# node-base.net
KiCad netlist of a schematic drawn in EAGLE
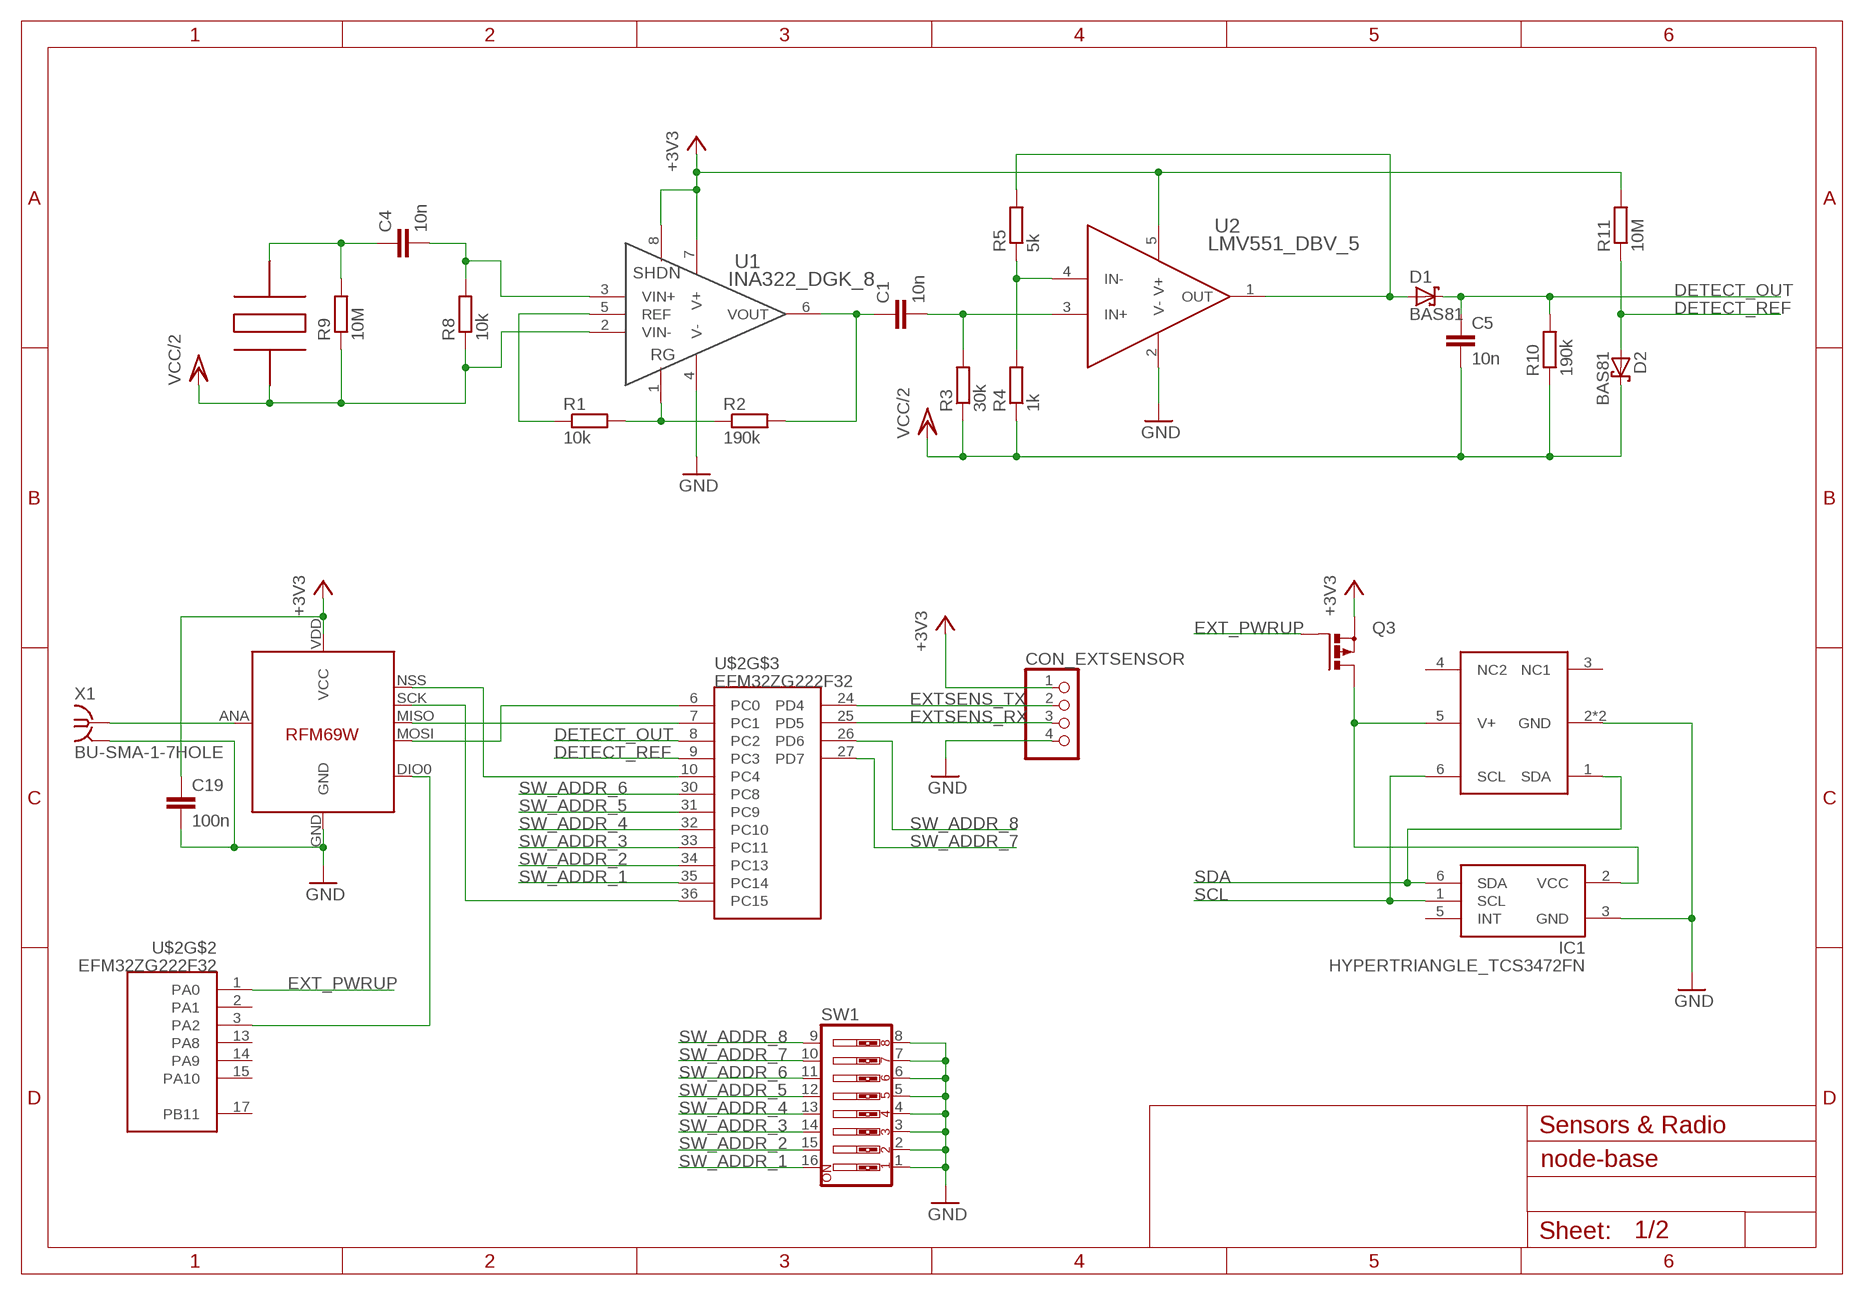
[diagram p0: schematic, sheet 1]
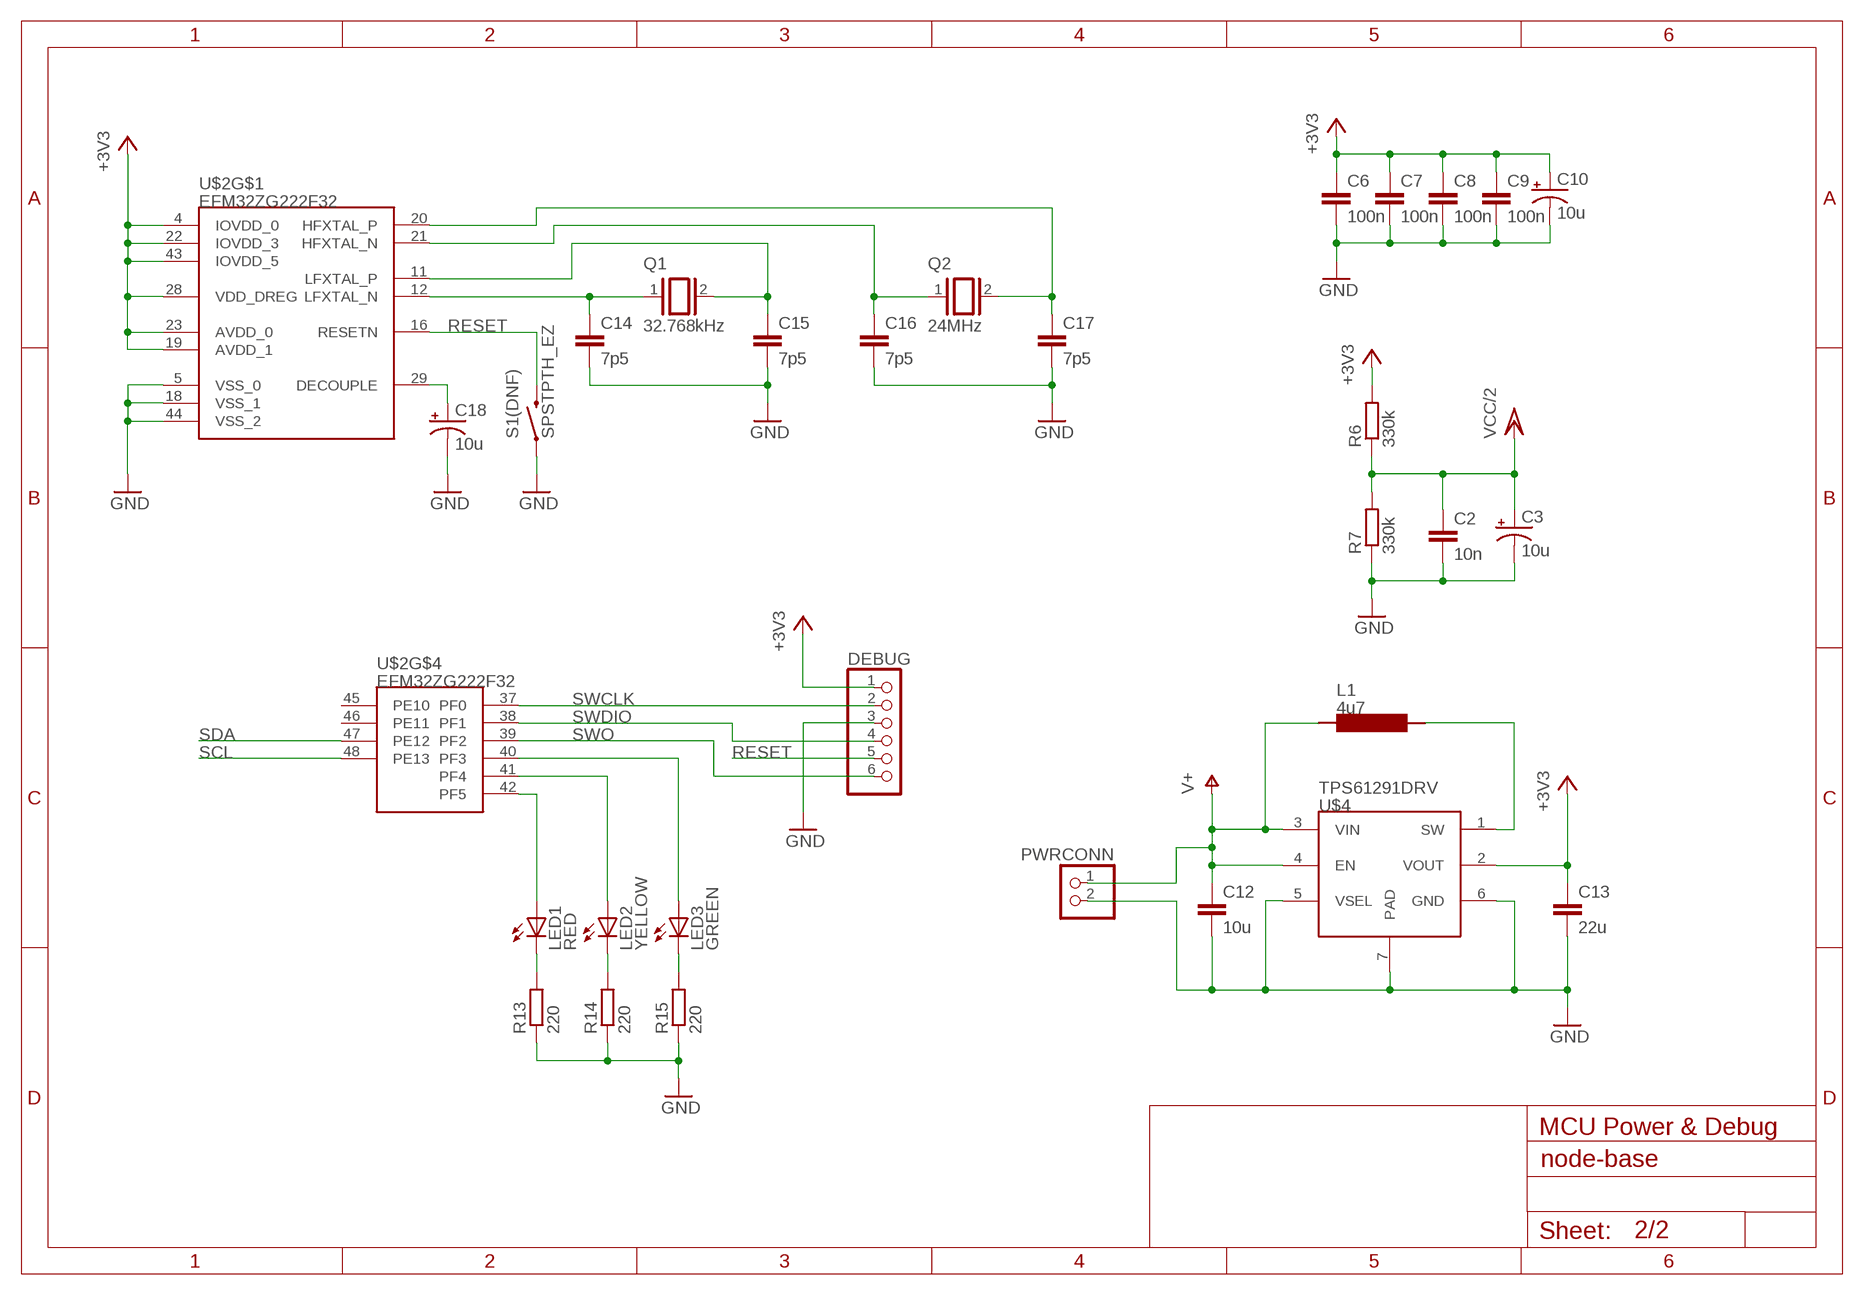
[diagram p1: schematic, sheet 2]

(export (version "E")
  (design (tool "Eeschema 10.0.6"))
  (components
    (comp (ref "C1")
      (value "10n")
      (footprint "eagle-import:CAP-PTH-SMALL")
      (libsource (lib "eagle-import") (part "CAPPTH"))
    )
    (comp (ref "C4")
      (value "10n")
      (footprint "eagle-import:CAP-PTH-SMALL")
      (libsource (lib "eagle-import") (part "CAPPTH"))
    )
    (comp (ref "C5")
      (value "10n")
      (footprint "eagle-import:CAP-PTH-SMALL")
      (libsource (lib "eagle-import") (part "CAPPTH"))
    )
    (comp (ref "C19")
      (value "100n")
      (footprint "eagle-import:CAP-PTH-SMALL")
      (libsource (lib "eagle-import") (part "CAPPTH"))
    )
    (comp (ref "CON_EXTSENSOR")
      (value "PINHD-1X4")
      (footprint "eagle-import:1X04")
      (libsource (lib "eagle-import") (part "PINHD-1X4"))
    )
    (comp (ref "D1")
      (value "BAS81")
      (footprint "eagle-import:DO35-7")
      (libsource (lib "eagle-import") (part "SCHOTTKY-DIODEDO35-7"))
    )
    (comp (ref "D2")
      (value "BAS81")
      (footprint "eagle-import:DO35-7")
      (libsource (lib "eagle-import") (part "SCHOTTKY-DIODEDO35-7"))
    )
    (comp (ref "IC1")
      (value "HYPERTRIANGLE_TCS3472FN")
      (footprint "eagle-import:HYPERTRIANGLE_DFN-6")
      (libsource (lib "eagle-import") (part "HYPERTRIANGLE_TCS3472FN"))
    )
    (comp (ref "Q3")
      (value "PMOSFET_PTO220BH")
      (footprint "eagle-import:TO220BH")
      (libsource (lib "eagle-import") (part "PMOSFET_PTO220BH"))
    )
    (comp (ref "R1")
      (value "10k")
      (footprint "eagle-import:0204_7")
      (libsource (lib "eagle-import") (part "R-EU_0204/7"))
    )
    (comp (ref "R2")
      (value "190k")
      (footprint "eagle-import:0204_7")
      (libsource (lib "eagle-import") (part "R-EU_0204/7"))
    )
    (comp (ref "R3")
      (value "30k")
      (footprint "eagle-import:0204_7")
      (libsource (lib "eagle-import") (part "R-EU_0204/7"))
    )
    (comp (ref "R4")
      (value "1k")
      (footprint "eagle-import:0204_7")
      (libsource (lib "eagle-import") (part "R-EU_0204/7"))
    )
    (comp (ref "R5")
      (value "5k")
      (footprint "eagle-import:0204_7")
      (libsource (lib "eagle-import") (part "R-EU_0204/7"))
    )
    (comp (ref "R8")
      (value "10k")
      (footprint "eagle-import:0204_7")
      (libsource (lib "eagle-import") (part "R-EU_0204/7"))
    )
    (comp (ref "R9")
      (value "10M")
      (footprint "eagle-import:0204_7")
      (libsource (lib "eagle-import") (part "R-EU_0204/7"))
    )
    (comp (ref "R10")
      (value "190k")
      (footprint "eagle-import:0204_7")
      (libsource (lib "eagle-import") (part "R-EU_0204/7"))
    )
    (comp (ref "R11")
      (value "10M")
      (footprint "eagle-import:0204_7")
      (libsource (lib "eagle-import") (part "R-EU_0204/7"))
    )
    (comp (ref "RADIO")
      (value "RFM69")
      (footprint "eagle-import:RFM69W-MINPADS")
      (libsource (lib "eagle-import") (part "RFM69"))
    )
    (comp (ref "SW1")
      (value "SW_DIP-8")
      (footprint "eagle-import:DIPSWITCH-08")
      (libsource (lib "eagle-import") (part "SW_DIP-8"))
    )
    (comp (ref "U$1")
      (value "PIEZOWIREHEADER")
      (footprint "eagle-import:1X02")
      (libsource (lib "eagle-import") (part "PIEZOWIREHEADER"))
    )
    (comp (ref "U$2")
      (value "EFM32ZG222F32")
      (footprint "eagle-import:QFP48")
      (libsource (lib "eagle-import") (part "EFM32ZG222F32"))
    )
    (comp (ref "U$3")
      (value "SHT21")
      (footprint "eagle-import:SHT21")
      (libsource (lib "eagle-import") (part "SHT21"))
    )
    (comp (ref "U1")
      (value "INA322_DGK_8")
      (footprint "eagle-import:DGK8")
      (fields
        (field (name "GENERIC_PART_NUMBER") "INA322")
        (field (name "MANUFACTURER") "Texas Instruments")
        (field (name "MANUFACTURER_PART_NUMBER") "ina322_dgk_8")
      )
      (libsource (lib "eagle-import") (part "INA322_DGK_8"))
    )
    (comp (ref "U2")
      (value "LMV551_DBV_5")
      (footprint "eagle-import:MF05A")
      (libsource (lib "eagle-import") (part "LMV551_DBV_5"))
    )
    (comp (ref "X1")
      (value "BU-SMA-1-7HOLE")
      (footprint "eagle-import:SMA_1-7HOLES")
      (libsource (lib "eagle-import") (part "BU-SMA-1-7HOLE"))
    )
    (comp (ref "C2")
      (value "10n")
      (footprint "eagle-import:CAP-PTH-SMALL")
      (libsource (lib "eagle-import") (part "CAPPTH"))
    )
    (comp (ref "C3")
      (value "10u")
      (footprint "eagle-import:CPOL-RADIAL-10UF-25V")
      (libsource (lib "eagle-import") (part "CAP_POLPTH2"))
    )
    (comp (ref "C6")
      (value "100n")
      (footprint "eagle-import:CAP-PTH-SMALL")
      (libsource (lib "eagle-import") (part "CAPPTH"))
    )
    (comp (ref "C7")
      (value "100n")
      (footprint "eagle-import:CAP-PTH-5MM")
      (libsource (lib "eagle-import") (part "CAPPTH1"))
    )
    (comp (ref "C8")
      (value "100n")
      (footprint "eagle-import:CAP-PTH-SMALL")
      (libsource (lib "eagle-import") (part "CAPPTH"))
    )
    (comp (ref "C9")
      (value "100n")
      (footprint "eagle-import:CAP-PTH-SMALL")
      (libsource (lib "eagle-import") (part "CAPPTH"))
    )
    (comp (ref "C10")
      (value "10u")
      (footprint "eagle-import:CPOL-RADIAL-10UF-25V")
      (libsource (lib "eagle-import") (part "CAP_POLPTH2"))
    )
    (comp (ref "C12")
      (value "10u")
      (footprint "eagle-import:1206")
      (libsource (lib "eagle-import") (part "CAP1206"))
    )
    (comp (ref "C13")
      (value "22u")
      (footprint "eagle-import:1206")
      (libsource (lib "eagle-import") (part "CAP1206"))
    )
    (comp (ref "C14")
      (value "7p5")
      (footprint "eagle-import:CAP-PTH-SMALL")
      (libsource (lib "eagle-import") (part "CAPPTH"))
    )
    (comp (ref "C15")
      (value "7p5")
      (footprint "eagle-import:CAP-PTH-SMALL")
      (libsource (lib "eagle-import") (part "CAPPTH"))
    )
    (comp (ref "C16")
      (value "7p5")
      (footprint "eagle-import:CAP-PTH-SMALL")
      (libsource (lib "eagle-import") (part "CAPPTH"))
    )
    (comp (ref "C17")
      (value "7p5")
      (footprint "eagle-import:CAP-PTH-SMALL")
      (libsource (lib "eagle-import") (part "CAPPTH"))
    )
    (comp (ref "C18")
      (value "10u")
      (footprint "eagle-import:CPOL-RADIAL-10UF-25V")
      (libsource (lib "eagle-import") (part "CAP_POLPTH2"))
    )
    (comp (ref "DEBUG")
      (value "PINHD-1X6")
      (footprint "eagle-import:1X06")
      (libsource (lib "eagle-import") (part "PINHD-1X6"))
    )
    (comp (ref "L1")
      (value "4u7")
      (footprint "eagle-import:LTF5022")
      (libsource (lib "eagle-import") (part "LTF5022"))
    )
    (comp (ref "LED1")
      (value "RED")
      (footprint "eagle-import:LED3MM")
      (libsource (lib "eagle-import") (part "LED3MM"))
    )
    (comp (ref "LED2")
      (value "YELLOW")
      (footprint "eagle-import:LED3MM")
      (libsource (lib "eagle-import") (part "LED3MM"))
    )
    (comp (ref "LED3")
      (value "GREEN")
      (footprint "eagle-import:LED3MM")
      (libsource (lib "eagle-import") (part "LED3MM"))
    )
    (comp (ref "PWRCONN")
      (value "PINHD-1X2")
      (footprint "eagle-import:1X02")
      (libsource (lib "eagle-import") (part "PINHD-1X2"))
    )
    (comp (ref "Q1")
      (value "32.768kHz")
      (footprint "eagle-import:QS")
      (libsource (lib "eagle-import") (part "XTAL/S"))
    )
    (comp (ref "Q2")
      (value "24MHz")
      (footprint "eagle-import:QS")
      (libsource (lib "eagle-import") (part "XTAL/S"))
    )
    (comp (ref "R6")
      (value "330k")
      (footprint "eagle-import:0204_7")
      (libsource (lib "eagle-import") (part "R-EU_0204/7"))
    )
    (comp (ref "R7")
      (value "330k")
      (footprint "eagle-import:0204_7")
      (libsource (lib "eagle-import") (part "R-EU_0204/7"))
    )
    (comp (ref "R13")
      (value "220")
      (footprint "eagle-import:0204_7")
      (libsource (lib "eagle-import") (part "R-EU_0204/7"))
    )
    (comp (ref "R14")
      (value "220")
      (footprint "eagle-import:0204_7")
      (libsource (lib "eagle-import") (part "R-EU_0204/7"))
    )
    (comp (ref "R15")
      (value "220")
      (footprint "eagle-import:0204_7")
      (libsource (lib "eagle-import") (part "R-EU_0204/7"))
    )
    (comp (ref "S1(DNF)")
      (value "SPSTPTH_EZ")
      (footprint "eagle-import:TACTILE-PTH-EZ")
      (libsource (lib "eagle-import") (part "SPSTPTH_EZ"))
    )
    (comp (ref "U$4")
      (value "TPS61291DRV")
      (footprint "eagle-import:DRV0006A")
      (libsource (lib "eagle-import") (part "TPS61291DRV"))
    )
  )
  (nets
    (net (code "1") (name "+3V3") (class "Default")
      (node (ref "C10") (pin "1") (pinfunction "+_1") (pintype "passive"))
      (node (ref "C13") (pin "1") (pinfunction "1_1") (pintype "passive"))
      (node (ref "C19") (pin "1") (pinfunction "1_1") (pintype "passive"))
      (node (ref "C6") (pin "1") (pinfunction "1_1") (pintype "passive"))
      (node (ref "C7") (pin "1") (pinfunction "1_1") (pintype "passive"))
      (node (ref "C8") (pin "1") (pinfunction "1_1") (pintype "passive"))
      (node (ref "C9") (pin "1") (pinfunction "1_1") (pintype "passive"))
      (node (ref "CON_EXTSENSOR") (pin "1") (pinfunction "1_1") (pintype "passive"))
      (node (ref "DEBUG") (pin "1") (pinfunction "1_1") (pintype "passive"))
      (node (ref "Q3") (pin "S") (pinfunction "S_S") (pintype "passive"))
      (node (ref "R11") (pin "2") (pinfunction "2_2") (pintype "passive"))
      (node (ref "R6") (pin "2") (pinfunction "2_2") (pintype "passive"))
      (node (ref "RADIO") (pin "VDD") (pinfunction "VCC_VDD") (pintype "power_in"))
      (node (ref "U$2") (pin "19") (pinfunction "AVDD_1_19") (pintype "power_in"))
      (node (ref "U$2") (pin "22") (pinfunction "IOVDD_3_22") (pintype "power_in"))
      (node (ref "U$2") (pin "23") (pinfunction "AVDD_0_23") (pintype "power_in"))
      (node (ref "U$2") (pin "28") (pinfunction "VDD_DREG_28") (pintype "power_in"))
      (node (ref "U$2") (pin "4") (pinfunction "IOVDD_0_4") (pintype "power_in"))
      (node (ref "U$2") (pin "43") (pinfunction "IOVDD_5_43") (pintype "power_in"))
      (node (ref "U$4") (pin "2") (pinfunction "VOUT_2") (pintype "bidirectional"))
      (node (ref "U1") (pin "7") (pinfunction "V+_7") (pintype "power_in"))
      (node (ref "U1") (pin "8") (pinfunction "SHDN_8") (pintype "passive"))
      (node (ref "U2") (pin "5") (pinfunction "V+_5") (pintype "power_in"))
    )
    (net (code "2") (name "DETECT_OUT") (class "Default")
      (node (ref "C5") (pin "1") (pinfunction "1_1") (pintype "passive"))
      (node (ref "D1") (pin "C") (pinfunction "C_C") (pintype "passive"))
      (node (ref "R10") (pin "2") (pinfunction "2_2") (pintype "passive"))
      (node (ref "U$2") (pin "8") (pinfunction "PC2_8") (pintype "bidirectional"))
    )
    (net (code "3") (name "DETECT_REF") (class "Default")
      (node (ref "D2") (pin "A") (pinfunction "A_A") (pintype "passive"))
      (node (ref "R11") (pin "1") (pinfunction "1_1") (pintype "passive"))
      (node (ref "U$2") (pin "9") (pinfunction "PC3_9") (pintype "bidirectional"))
    )
    (net (code "4") (name "EXTSENS_RX") (class "Default")
      (node (ref "CON_EXTSENSOR") (pin "3") (pinfunction "3_3") (pintype "passive"))
      (node (ref "U$2") (pin "25") (pinfunction "PD5_25") (pintype "bidirectional"))
    )
    (net (code "5") (name "EXTSENS_TX") (class "Default")
      (node (ref "CON_EXTSENSOR") (pin "2") (pinfunction "2_2") (pintype "passive"))
      (node (ref "U$2") (pin "24") (pinfunction "PD4_24") (pintype "bidirectional"))
    )
    (net (code "6") (name "EXT_PWRUP") (class "Default")
      (node (ref "Q3") (pin "G") (pinfunction "G_G") (pintype "passive"))
      (node (ref "U$2") (pin "1") (pinfunction "PA0_1") (pintype "bidirectional"))
    )
    (net (code "7") (name "GND") (class "Default")
      (node (ref "C10") (pin "2") (pinfunction "-_2") (pintype "passive"))
      (node (ref "C12") (pin "2") (pinfunction "2_2") (pintype "passive"))
      (node (ref "C13") (pin "2") (pinfunction "2_2") (pintype "passive"))
      (node (ref "C14") (pin "2") (pinfunction "2_2") (pintype "passive"))
      (node (ref "C15") (pin "2") (pinfunction "2_2") (pintype "passive"))
      (node (ref "C16") (pin "2") (pinfunction "2_2") (pintype "passive"))
      (node (ref "C17") (pin "2") (pinfunction "2_2") (pintype "passive"))
      (node (ref "C18") (pin "2") (pinfunction "-_2") (pintype "passive"))
      (node (ref "C19") (pin "2") (pinfunction "2_2") (pintype "passive"))
      (node (ref "C2") (pin "2") (pinfunction "2_2") (pintype "passive"))
      (node (ref "C3") (pin "2") (pinfunction "-_2") (pintype "passive"))
      (node (ref "C6") (pin "2") (pinfunction "2_2") (pintype "passive"))
      (node (ref "C7") (pin "2") (pinfunction "2_2") (pintype "passive"))
      (node (ref "C8") (pin "2") (pinfunction "2_2") (pintype "passive"))
      (node (ref "C9") (pin "2") (pinfunction "2_2") (pintype "passive"))
      (node (ref "CON_EXTSENSOR") (pin "4") (pinfunction "4_4") (pintype "passive"))
      (node (ref "DEBUG") (pin "3") (pinfunction "3_3") (pintype "passive"))
      (node (ref "IC1") (pin "3") (pinfunction "GND_3") (pintype "power_in"))
      (node (ref "PWRCONN") (pin "2") (pinfunction "2_2") (pintype "passive"))
      (node (ref "R13") (pin "1") (pinfunction "1_1") (pintype "passive"))
      (node (ref "R14") (pin "1") (pinfunction "1_1") (pintype "passive"))
      (node (ref "R15") (pin "1") (pinfunction "1_1") (pintype "passive"))
      (node (ref "R7") (pin "1") (pinfunction "1_1") (pintype "passive"))
      (node (ref "RADIO") (pin "GND") (pinfunction "GND_GND") (pintype "power_in"))
      (node (ref "S1(DNF)") (pin "1") (pinfunction "1_1") (pintype "passive"))
      (node (ref "SW1") (pin "1") (pinfunction "1_1") (pintype "passive"))
      (node (ref "SW1") (pin "2") (pinfunction "2_2") (pintype "passive"))
      (node (ref "SW1") (pin "3") (pinfunction "3_3") (pintype "passive"))
      (node (ref "SW1") (pin "4") (pinfunction "4_4") (pintype "passive"))
      (node (ref "SW1") (pin "5") (pinfunction "5_5") (pintype "passive"))
      (node (ref "SW1") (pin "6") (pinfunction "6_6") (pintype "passive"))
      (node (ref "SW1") (pin "7") (pinfunction "7_7") (pintype "passive"))
      (node (ref "SW1") (pin "8") (pinfunction "8_8") (pintype "passive"))
      (node (ref "U$2") (pin "18") (pinfunction "VSS_1_18") (pintype "bidirectional"))
      (node (ref "U$2") (pin "44") (pinfunction "VSS_2_44") (pintype "bidirectional"))
      (node (ref "U$2") (pin "5") (pinfunction "VSS_0_5") (pintype "bidirectional"))
      (node (ref "U$3") (pin "2") (pinfunction "GND_2") (pintype "bidirectional"))
      (node (ref "U$3") (pin "P$1") (pinfunction "GND_P$1") (pintype "bidirectional"))
      (node (ref "U$4") (pin "5") (pinfunction "VSEL_5") (pintype "bidirectional"))
      (node (ref "U$4") (pin "6") (pinfunction "GND_6") (pintype "bidirectional"))
      (node (ref "U$4") (pin "7") (pinfunction "PAD_7") (pintype "bidirectional"))
      (node (ref "U1") (pin "4") (pinfunction "V-_4") (pintype "power_in"))
      (node (ref "U2") (pin "2") (pinfunction "V-_2") (pintype "power_in"))
      (node (ref "X1") (pin "2") (pinfunction "2_2") (pintype "passive"))
      (node (ref "X1") (pin "3") (pinfunction "2_3") (pintype "passive"))
      (node (ref "X1") (pin "4") (pinfunction "2_4") (pintype "passive"))
      (node (ref "X1") (pin "5") (pinfunction "2_5") (pintype "passive"))
    )
    (net (code "8") (name "Net-(C18-+)") (class "Default")
      (node (ref "C18") (pin "1") (pinfunction "+_1") (pintype "passive"))
      (node (ref "U$2") (pin "29") (pinfunction "DECOUPLE_29") (pintype "power_in"))
    )
    (net (code "9") (name "Net-(IC1-VCC)") (class "Default")
      (node (ref "IC1") (pin "2") (pinfunction "VCC_2") (pintype "power_in"))
      (node (ref "Q3") (pin "D") (pinfunction "D_D") (pintype "passive"))
      (node (ref "U$3") (pin "5") (pinfunction "V+_5") (pintype "bidirectional"))
    )
    (net (code "10") (name "Net-(LED1-C)") (class "Default")
      (node (ref "LED1") (pin "K") (pinfunction "C_K") (pintype "passive"))
      (node (ref "R13") (pin "2") (pinfunction "2_2") (pintype "passive"))
    )
    (net (code "11") (name "Net-(LED2-C)") (class "Default")
      (node (ref "LED2") (pin "K") (pinfunction "C_K") (pintype "passive"))
      (node (ref "R14") (pin "2") (pinfunction "2_2") (pintype "passive"))
    )
    (net (code "12") (name "Net-(LED3-C)") (class "Default")
      (node (ref "LED3") (pin "K") (pinfunction "C_K") (pintype "passive"))
      (node (ref "R15") (pin "2") (pinfunction "2_2") (pintype "passive"))
    )
    (net (code "13") (name "Net-(RADIO-ANT)") (class "Default")
      (node (ref "RADIO") (pin "ANA") (pinfunction "ANT_ANA") (pintype "passive"))
      (node (ref "X1") (pin "1") (pinfunction "1_1") (pintype "passive"))
    )
    (net (code "14") (name "Net-(RADIO-SEL)") (class "Default")
      (node (ref "RADIO") (pin "NSS") (pinfunction "SEL_NSS") (pintype "input"))
      (node (ref "U$2") (pin "10") (pinfunction "PC4_10") (pintype "bidirectional"))
    )
    (net (code "15") (name "Net-(U$1-S+)") (class "Default")
      (node (ref "C4") (pin "1") (pinfunction "1_1") (pintype "passive"))
      (node (ref "R9") (pin "2") (pinfunction "2_2") (pintype "passive"))
      (node (ref "U$1") (pin "1") (pinfunction "S+_1") (pintype "passive"))
    )
    (net (code "16") (name "Net-(U$2A-HFXTAL_N)") (class "Default")
      (node (ref "C16") (pin "1") (pinfunction "1_1") (pintype "passive"))
      (node (ref "Q2") (pin "1") (pinfunction "1_1") (pintype "passive"))
      (node (ref "U$2") (pin "21") (pinfunction "HFXTAL_N_21") (pintype "bidirectional"))
    )
    (net (code "17") (name "Net-(U$2A-HFXTAL_P)") (class "Default")
      (node (ref "C17") (pin "1") (pinfunction "1_1") (pintype "passive"))
      (node (ref "Q2") (pin "2") (pinfunction "2_2") (pintype "passive"))
      (node (ref "U$2") (pin "20") (pinfunction "HFXTAL_P_20") (pintype "bidirectional"))
    )
    (net (code "18") (name "Net-(U$2A-LFXTAL_N)") (class "Default")
      (node (ref "C14") (pin "1") (pinfunction "1_1") (pintype "passive"))
      (node (ref "Q1") (pin "1") (pinfunction "1_1") (pintype "passive"))
      (node (ref "U$2") (pin "12") (pinfunction "LFXTAL_N_12") (pintype "bidirectional"))
    )
    (net (code "19") (name "Net-(U$2A-LFXTAL_P)") (class "Default")
      (node (ref "C15") (pin "1") (pinfunction "1_1") (pintype "passive"))
      (node (ref "Q1") (pin "2") (pinfunction "2_2") (pintype "passive"))
      (node (ref "U$2") (pin "11") (pinfunction "LFXTAL_P_11") (pintype "bidirectional"))
    )
    (net (code "20") (name "Net-(U$2B-PA2)") (class "Default")
      (node (ref "RADIO") (pin "DIO0") (pinfunction "DIO0_DIO0") (pintype "open_collector"))
      (node (ref "U$2") (pin "3") (pinfunction "PA2_3") (pintype "bidirectional"))
    )
    (net (code "21") (name "Net-(U$2C-PC0)") (class "Default")
      (node (ref "RADIO") (pin "MOSI") (pinfunction "MOSI_MOSI") (pintype "output"))
      (node (ref "U$2") (pin "6") (pinfunction "PC0_6") (pintype "bidirectional"))
    )
    (net (code "22") (name "Net-(U$2C-PC1)") (class "Default")
      (node (ref "RADIO") (pin "MISO") (pinfunction "MISO_MISO") (pintype "input"))
      (node (ref "U$2") (pin "7") (pinfunction "PC1_7") (pintype "bidirectional"))
    )
    (net (code "23") (name "Net-(U$2C-PC15)") (class "Default")
      (node (ref "RADIO") (pin "SCK") (pinfunction "SCK_SCK") (pintype "input"))
      (node (ref "U$2") (pin "36") (pinfunction "PC15_36") (pintype "bidirectional"))
    )
    (net (code "24") (name "Net-(U$2D-PF3)") (class "Default")
      (node (ref "LED3") (pin "A") (pinfunction "A_A") (pintype "passive"))
      (node (ref "U$2") (pin "40") (pinfunction "PF3_40") (pintype "bidirectional"))
    )
    (net (code "25") (name "Net-(U$2D-PF4)") (class "Default")
      (node (ref "LED2") (pin "A") (pinfunction "A_A") (pintype "passive"))
      (node (ref "U$2") (pin "41") (pinfunction "PF4_41") (pintype "bidirectional"))
    )
    (net (code "26") (name "Net-(U$2D-PF5)") (class "Default")
      (node (ref "LED1") (pin "A") (pinfunction "A_A") (pintype "passive"))
      (node (ref "U$2") (pin "42") (pinfunction "PF5_42") (pintype "bidirectional"))
    )
    (net (code "27") (name "Net-(U$4-SW)") (class "Default")
      (node (ref "L1") (pin "2") (pinfunction "2_2") (pintype "passive"))
      (node (ref "U$4") (pin "1") (pinfunction "SW_1") (pintype "bidirectional"))
    )
    (net (code "28") (name "Net-(U1-REF)") (class "Default")
      (node (ref "R1") (pin "1") (pinfunction "1_1") (pintype "passive"))
      (node (ref "U1") (pin "5") (pinfunction "REF_5") (pintype "passive"))
    )
    (net (code "29") (name "Net-(U1-RG)") (class "Default")
      (node (ref "R1") (pin "2") (pinfunction "2_2") (pintype "passive"))
      (node (ref "R2") (pin "1") (pinfunction "1_1") (pintype "passive"))
      (node (ref "U1") (pin "1") (pinfunction "RG_1") (pintype "passive"))
    )
    (net (code "30") (name "Net-(U1-VIN+)") (class "Default")
      (node (ref "C4") (pin "2") (pinfunction "2_2") (pintype "passive"))
      (node (ref "R8") (pin "2") (pinfunction "2_2") (pintype "passive"))
      (node (ref "U1") (pin "3") (pinfunction "VIN+_3") (pintype "input"))
    )
    (net (code "31") (name "Net-(U1-VOUT)") (class "Default")
      (node (ref "C1") (pin "1") (pinfunction "1_1") (pintype "passive"))
      (node (ref "R2") (pin "2") (pinfunction "2_2") (pintype "passive"))
      (node (ref "U1") (pin "6") (pinfunction "VOUT_6") (pintype "output"))
    )
    (net (code "32") (name "Net-(U2-IN+)") (class "Default")
      (node (ref "C1") (pin "2") (pinfunction "2_2") (pintype "passive"))
      (node (ref "R3") (pin "2") (pinfunction "2_2") (pintype "passive"))
      (node (ref "U2") (pin "3") (pinfunction "IN+_3") (pintype "input"))
    )
    (net (code "33") (name "Net-(U2-IN-)") (class "Default")
      (node (ref "R4") (pin "2") (pinfunction "2_2") (pintype "passive"))
      (node (ref "R5") (pin "1") (pinfunction "1_1") (pintype "passive"))
      (node (ref "U2") (pin "4") (pinfunction "IN-_4") (pintype "input"))
    )
    (net (code "34") (name "Net-(U2-OUT)") (class "Default")
      (node (ref "D1") (pin "A") (pinfunction "A_A") (pintype "passive"))
      (node (ref "R5") (pin "2") (pinfunction "2_2") (pintype "passive"))
      (node (ref "U2") (pin "1") (pinfunction "OUT_1") (pintype "output"))
    )
    (net (code "35") (name "RESET") (class "Default")
      (node (ref "DEBUG") (pin "5") (pinfunction "5_5") (pintype "passive"))
      (node (ref "S1(DNF)") (pin "3") (pinfunction "2_3") (pintype "passive"))
      (node (ref "U$2") (pin "16") (pinfunction "RESETN_16") (pintype "power_in"))
    )
    (net (code "36") (name "SCL") (class "Default")
      (node (ref "IC1") (pin "1") (pinfunction "SCL_1") (pintype "bidirectional"))
      (node (ref "U$2") (pin "48") (pinfunction "PE13_48") (pintype "bidirectional"))
      (node (ref "U$3") (pin "6") (pinfunction "SCL_6") (pintype "bidirectional"))
    )
    (net (code "37") (name "SDA") (class "Default")
      (node (ref "IC1") (pin "6") (pinfunction "SDA_6") (pintype "bidirectional"))
      (node (ref "U$2") (pin "47") (pinfunction "PE12_47") (pintype "bidirectional"))
      (node (ref "U$3") (pin "1") (pinfunction "SDA_1") (pintype "bidirectional"))
    )
    (net (code "38") (name "SWCLK") (class "Default")
      (node (ref "DEBUG") (pin "2") (pinfunction "2_2") (pintype "passive"))
      (node (ref "U$2") (pin "37") (pinfunction "PF0_37") (pintype "bidirectional"))
    )
    (net (code "39") (name "SWDIO") (class "Default")
      (node (ref "DEBUG") (pin "4") (pinfunction "4_4") (pintype "passive"))
      (node (ref "U$2") (pin "38") (pinfunction "PF1_38") (pintype "bidirectional"))
    )
    (net (code "40") (name "SWO") (class "Default")
      (node (ref "DEBUG") (pin "6") (pinfunction "6_6") (pintype "passive"))
      (node (ref "U$2") (pin "39") (pinfunction "PF2_39") (pintype "bidirectional"))
    )
    (net (code "41") (name "SW_ADDR_1") (class "Default")
      (node (ref "SW1") (pin "16") (pinfunction "16_16") (pintype "passive"))
      (node (ref "U$2") (pin "35") (pinfunction "PC14_35") (pintype "bidirectional"))
    )
    (net (code "42") (name "SW_ADDR_2") (class "Default")
      (node (ref "SW1") (pin "15") (pinfunction "15_15") (pintype "passive"))
      (node (ref "U$2") (pin "34") (pinfunction "PC13_34") (pintype "bidirectional"))
    )
    (net (code "43") (name "SW_ADDR_3") (class "Default")
      (node (ref "SW1") (pin "14") (pinfunction "14_14") (pintype "passive"))
      (node (ref "U$2") (pin "33") (pinfunction "PC11_33") (pintype "bidirectional"))
    )
    (net (code "44") (name "SW_ADDR_4") (class "Default")
      (node (ref "SW1") (pin "13") (pinfunction "13_13") (pintype "passive"))
      (node (ref "U$2") (pin "32") (pinfunction "PC10_32") (pintype "bidirectional"))
    )
    (net (code "45") (name "SW_ADDR_5") (class "Default")
      (node (ref "SW1") (pin "12") (pinfunction "12_12") (pintype "passive"))
      (node (ref "U$2") (pin "31") (pinfunction "PC9_31") (pintype "bidirectional"))
    )
    (net (code "46") (name "SW_ADDR_6") (class "Default")
      (node (ref "SW1") (pin "11") (pinfunction "11_11") (pintype "passive"))
      (node (ref "U$2") (pin "30") (pinfunction "PC8_30") (pintype "bidirectional"))
    )
    (net (code "47") (name "SW_ADDR_7") (class "Default")
      (node (ref "SW1") (pin "10") (pinfunction "10_10") (pintype "passive"))
      (node (ref "U$2") (pin "27") (pinfunction "PD7_27") (pintype "bidirectional"))
    )
    (net (code "48") (name "SW_ADDR_8") (class "Default")
      (node (ref "SW1") (pin "9") (pinfunction "9_9") (pintype "passive"))
      (node (ref "U$2") (pin "26") (pinfunction "PD6_26") (pintype "bidirectional"))
    )
    (net (code "49") (name "V+") (class "Default")
      (node (ref "C12") (pin "1") (pinfunction "1_1") (pintype "passive"))
      (node (ref "L1") (pin "1") (pinfunction "1_1") (pintype "passive"))
      (node (ref "PWRCONN") (pin "1") (pinfunction "1_1") (pintype "passive"))
      (node (ref "U$4") (pin "3") (pinfunction "VIN_3") (pintype "bidirectional"))
      (node (ref "U$4") (pin "4") (pinfunction "EN_4") (pintype "bidirectional"))
    )
    (net (code "50") (name "VCC{slash}2") (class "Default")
      (node (ref "C2") (pin "1") (pinfunction "1_1") (pintype "passive"))
      (node (ref "C3") (pin "1") (pinfunction "+_1") (pintype "passive"))
      (node (ref "C5") (pin "2") (pinfunction "2_2") (pintype "passive"))
      (node (ref "D2") (pin "C") (pinfunction "C_C") (pintype "passive"))
      (node (ref "R10") (pin "1") (pinfunction "1_1") (pintype "passive"))
      (node (ref "R3") (pin "1") (pinfunction "1_1") (pintype "passive"))
      (node (ref "R4") (pin "1") (pinfunction "1_1") (pintype "passive"))
      (node (ref "R6") (pin "1") (pinfunction "1_1") (pintype "passive"))
      (node (ref "R7") (pin "2") (pinfunction "2_2") (pintype "passive"))
      (node (ref "R8") (pin "1") (pinfunction "1_1") (pintype "passive"))
      (node (ref "R9") (pin "1") (pinfunction "1_1") (pintype "passive"))
      (node (ref "U$1") (pin "2") (pinfunction "S-_2") (pintype "passive"))
      (node (ref "U1") (pin "2") (pinfunction "VIN-_2") (pintype "input"))
    )
    (net (code "51") (name "unconnected-(IC1-INT-Pad5)") (class "Default")
      (node (ref "IC1") (pin "5") (pinfunction "INT_5") (pintype "output"))
    )
    (net (code "52") (name "unconnected-(U$2B-PA1-Pad2)") (class "Default")
      (node (ref "U$2") (pin "2") (pinfunction "PA1_2") (pintype "bidirectional"))
    )
    (net (code "53") (name "unconnected-(U$2B-PA8-Pad13)") (class "Default")
      (node (ref "U$2") (pin "13") (pinfunction "PA8_13") (pintype "bidirectional"))
    )
    (net (code "54") (name "unconnected-(U$2B-PA9-Pad14)") (class "Default")
      (node (ref "U$2") (pin "14") (pinfunction "PA9_14") (pintype "bidirectional"))
    )
    (net (code "55") (name "unconnected-(U$2B-PA10-Pad15)") (class "Default")
      (node (ref "U$2") (pin "15") (pinfunction "PA10_15") (pintype "bidirectional"))
    )
    (net (code "56") (name "unconnected-(U$2B-PB11-Pad17)") (class "Default")
      (node (ref "U$2") (pin "17") (pinfunction "PB11_17") (pintype "bidirectional"))
    )
    (net (code "57") (name "unconnected-(U$2D-PE10-Pad45)") (class "Default")
      (node (ref "U$2") (pin "45") (pinfunction "PE10_45") (pintype "bidirectional"))
    )
    (net (code "58") (name "unconnected-(U$2D-PE11-Pad46)") (class "Default")
      (node (ref "U$2") (pin "46") (pinfunction "PE11_46") (pintype "bidirectional"))
    )
    (net (code "59") (name "unconnected-(U$3-NC1-Pad3)") (class "Default")
      (node (ref "U$3") (pin "3") (pinfunction "NC1_3") (pintype "bidirectional"))
    )
    (net (code "60") (name "unconnected-(U$3-NC2-Pad4)") (class "Default")
      (node (ref "U$3") (pin "4") (pinfunction "NC2_4") (pintype "bidirectional"))
    )
  )
)
